# LoRa_1W_Breakout_433MHz.net
KiCad netlist of a schematic drawn in EAGLE
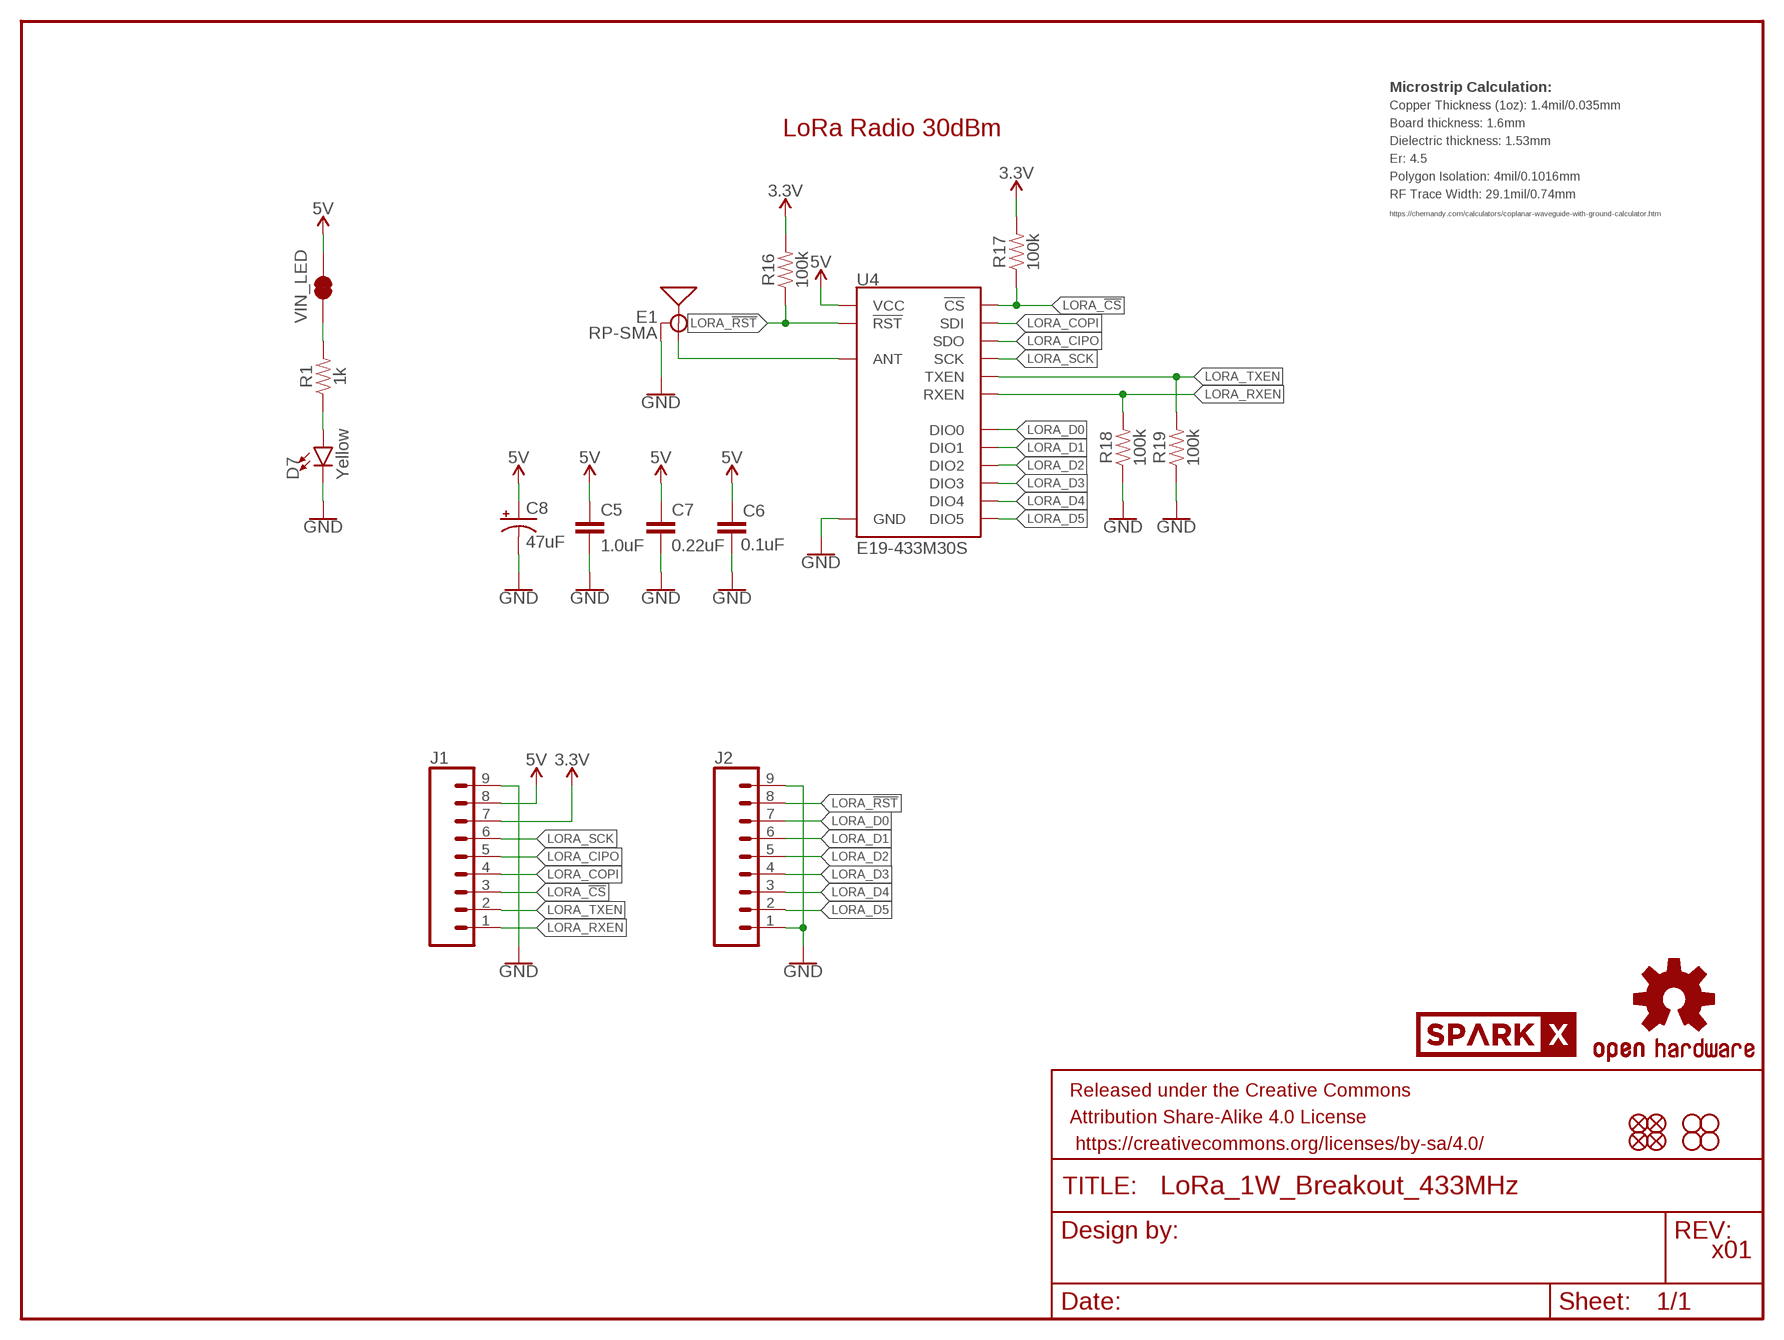
[diagram p0: schematic, sheet 1]

(export (version "E")
  (design (tool "Eeschema 10.0.6"))
  (components
    (comp (ref "C5")
      (value "1.0uF")
      (footprint "eagle-import:0603")
      (libsource (lib "eagle-import") (part "1.0UF-0603-16V-10%"))
    )
    (comp (ref "C6")
      (value "0.1uF")
      (footprint "eagle-import:0603")
      (libsource (lib "eagle-import") (part "0.1UF-0603-25V-(+80/-20%)"))
    )
    (comp (ref "C7")
      (value "0.22uF")
      (footprint "eagle-import:0603")
      (libsource (lib "eagle-import") (part "0.22UF-0603-25V-10%"))
    )
    (comp (ref "C8")
      (value "47uF")
      (footprint "eagle-import:EIA3528")
      (libsource (lib "eagle-import") (part "47UF-POLAR-EIA3528-10V-10%"))
    )
    (comp (ref "D7")
      (value "Yellow")
      (footprint "eagle-import:LED-0603")
      (libsource (lib "eagle-import") (part "LED-YELLOW0603"))
    )
    (comp (ref "E1")
      (value "RP-SMA")
      (footprint "eagle-import:SMA-EDGE")
      (libsource (lib "eagle-import") (part "ANTENNA-SMA-GROUNDEDEDGE_RPSMA"))
    )
    (comp (ref "FD1")
      (value "FIDUCIALUFIDUCIAL")
      (footprint "eagle-import:FIDUCIAL-MICRO")
      (libsource (lib "eagle-import") (part "FIDUCIALUFIDUCIAL"))
    )
    (comp (ref "FD2")
      (value "FIDUCIALUFIDUCIAL")
      (footprint "eagle-import:FIDUCIAL-MICRO")
      (libsource (lib "eagle-import") (part "FIDUCIALUFIDUCIAL"))
    )
    (comp (ref "FD3")
      (value "FIDUCIALUFIDUCIAL")
      (footprint "eagle-import:FIDUCIAL-MICRO")
      (libsource (lib "eagle-import") (part "FIDUCIALUFIDUCIAL"))
    )
    (comp (ref "FD4")
      (value "FIDUCIALUFIDUCIAL")
      (footprint "eagle-import:FIDUCIAL-MICRO")
      (libsource (lib "eagle-import") (part "FIDUCIALUFIDUCIAL"))
    )
    (comp (ref "FRAME2")
      (value "FRAME-LETTER")
      (footprint "eagle-import:CREATIVE_COMMONS")
      (libsource (lib "eagle-import") (part "FRAME-LETTER"))
    )
    (comp (ref "H1")
      (value "STAND-OFF")
      (footprint "eagle-import:STAND-OFF")
      (libsource (lib "eagle-import") (part "STAND-OFF"))
    )
    (comp (ref "H2")
      (value "STAND-OFF")
      (footprint "eagle-import:STAND-OFF")
      (libsource (lib "eagle-import") (part "STAND-OFF"))
    )
    (comp (ref "H3")
      (value "STAND-OFF")
      (footprint "eagle-import:STAND-OFF")
      (libsource (lib "eagle-import") (part "STAND-OFF"))
    )
    (comp (ref "H4")
      (value "STAND-OFF")
      (footprint "eagle-import:STAND-OFF")
      (libsource (lib "eagle-import") (part "STAND-OFF"))
    )
    (comp (ref "J1")
      (value "CONN_09NO_SILK")
      (footprint "eagle-import:1X09_NO_SILK")
      (libsource (lib "eagle-import") (part "CONN_09NO_SILK"))
    )
    (comp (ref "J2")
      (value "CONN_09NO_SILK")
      (footprint "eagle-import:1X09_NO_SILK")
      (libsource (lib "eagle-import") (part "CONN_09NO_SILK"))
    )
    (comp (ref "LOGO3")
      (value "OSHW-LOGOMINI")
      (footprint "eagle-import:OSHW-LOGO-MINI")
      (libsource (lib "eagle-import") (part "OSHW-LOGOMINI"))
    )
    (comp (ref "R1")
      (value "1k")
      (footprint "eagle-import:0603")
      (libsource (lib "eagle-import") (part "1KOHM-0603-1/10W-1%"))
    )
    (comp (ref "R16")
      (value "100k")
      (footprint "eagle-import:0603")
      (libsource (lib "eagle-import") (part "100KOHM-0603-1/10W-1%"))
    )
    (comp (ref "R17")
      (value "100k")
      (footprint "eagle-import:0603")
      (libsource (lib "eagle-import") (part "100KOHM-0603-1/10W-1%"))
    )
    (comp (ref "R18")
      (value "100k")
      (footprint "eagle-import:0603")
      (libsource (lib "eagle-import") (part "100KOHM-0603-1/10W-1%"))
    )
    (comp (ref "R19")
      (value "100k")
      (footprint "eagle-import:0603")
      (libsource (lib "eagle-import") (part "100KOHM-0603-1/10W-1%"))
    )
    (comp (ref "U$5")
      (value "SPARKX-LOGO5")
      (footprint "eagle-import:SPARKX-LARGE")
      (libsource (lib "eagle-import") (part "SPARKX-LOGO5"))
    )
    (comp (ref "U4")
      (value "E19-433M30S")
      (footprint "eagle-import:E19-433M30S")
      (libsource (lib "eagle-import") (part "LORA-E19433MHZ"))
    )
    (comp (ref "VIN_LED")
      (value "JUMPER-SMT_2_NC_TRACE_SILK")
      (footprint "eagle-import:SMT-JUMPER_2_NC_TRACE_SILK")
      (libsource (lib "eagle-import") (part "JUMPER-SMT_2_NC_TRACE_SILK"))
    )
  )
  (nets
    (net (code "1") (name "/LORA_~{CS}") (class "Default")
      (node (ref "J1") (pin "3") (pinfunction "3_3") (pintype "passive"))
      (node (ref "R17") (pin "1") (pinfunction "1_1") (pintype "passive"))
      (node (ref "U4") (pin "15") (pinfunction "~{CS}_15") (pintype "bidirectional"))
    )
    (net (code "2") (name "/LORA_~{RST}") (class "Default")
      (node (ref "J2") (pin "8") (pinfunction "8_8") (pintype "passive"))
      (node (ref "R16") (pin "1") (pinfunction "1_1") (pintype "passive"))
      (node (ref "U4") (pin "8") (pinfunction "~{RST}_8") (pintype "bidirectional"))
    )
    (net (code "3") (name "3.3V") (class "Default")
      (node (ref "J1") (pin "7") (pinfunction "7_7") (pintype "passive"))
      (node (ref "R16") (pin "2") (pinfunction "2_2") (pintype "passive"))
      (node (ref "R17") (pin "2") (pinfunction "2_2") (pintype "passive"))
    )
    (net (code "4") (name "5V") (class "Default")
      (node (ref "C5") (pin "1") (pinfunction "1_1") (pintype "passive"))
      (node (ref "C6") (pin "1") (pinfunction "1_1") (pintype "passive"))
      (node (ref "C7") (pin "1") (pinfunction "1_1") (pintype "passive"))
      (node (ref "C8") (pin "A") (pinfunction "+_A") (pintype "passive"))
      (node (ref "J1") (pin "8") (pinfunction "8_8") (pintype "passive"))
      (node (ref "U4") (pin "11") (pinfunction "VCC_11") (pintype "bidirectional"))
      (node (ref "VIN_LED") (pin "2") (pinfunction "2_2") (pintype "passive"))
    )
    (net (code "5") (name "GND") (class "Default")
      (node (ref "C5") (pin "2") (pinfunction "2_2") (pintype "passive"))
      (node (ref "C6") (pin "2") (pinfunction "2_2") (pintype "passive"))
      (node (ref "C7") (pin "2") (pinfunction "2_2") (pintype "passive"))
      (node (ref "C8") (pin "C") (pinfunction "-_C") (pintype "passive"))
      (node (ref "D7") (pin "C") (pinfunction "C_C") (pintype "passive"))
      (node (ref "E1") (pin "GND@0") (pinfunction "GND_GND@0") (pintype "bidirectional"))
      (node (ref "E1") (pin "GND@1") (pinfunction "GND_GND@1") (pintype "bidirectional"))
      (node (ref "E1") (pin "GND@2") (pinfunction "GND_GND@2") (pintype "bidirectional"))
      (node (ref "E1") (pin "GND@3") (pinfunction "GND_GND@3") (pintype "bidirectional"))
      (node (ref "J1") (pin "9") (pinfunction "9_9") (pintype "passive"))
      (node (ref "J2") (pin "1") (pinfunction "1_1") (pintype "passive"))
      (node (ref "J2") (pin "9") (pinfunction "9_9") (pintype "passive"))
      (node (ref "R18") (pin "1") (pinfunction "1_1") (pintype "passive"))
      (node (ref "R19") (pin "1") (pinfunction "1_1") (pintype "passive"))
      (node (ref "U4") (pin "1") (pinfunction "GND_1") (pintype "bidirectional"))
      (node (ref "U4") (pin "10") (pinfunction "GND_10") (pintype "bidirectional"))
      (node (ref "U4") (pin "18") (pinfunction "GND_18") (pintype "bidirectional"))
      (node (ref "U4") (pin "20") (pinfunction "GND_20") (pintype "bidirectional"))
      (node (ref "U4") (pin "21") (pinfunction "GND_21") (pintype "bidirectional"))
      (node (ref "U4") (pin "22") (pinfunction "GND_22") (pintype "bidirectional"))
      (node (ref "U4") (pin "9") (pinfunction "GND_9") (pintype "bidirectional"))
    )
    (net (code "6") (name "LORA_CIPO") (class "Default")
      (node (ref "J1") (pin "5") (pinfunction "5_5") (pintype "passive"))
      (node (ref "U4") (pin "13") (pinfunction "SDO_13") (pintype "bidirectional"))
    )
    (net (code "7") (name "LORA_COPI") (class "Default")
      (node (ref "J1") (pin "4") (pinfunction "4_4") (pintype "passive"))
      (node (ref "U4") (pin "14") (pinfunction "SDI_14") (pintype "bidirectional"))
    )
    (net (code "8") (name "LORA_D0") (class "Default")
      (node (ref "J2") (pin "7") (pinfunction "7_7") (pintype "passive"))
      (node (ref "U4") (pin "7") (pinfunction "DIO0_7") (pintype "bidirectional"))
    )
    (net (code "9") (name "LORA_D1") (class "Default")
      (node (ref "J2") (pin "6") (pinfunction "6_6") (pintype "passive"))
      (node (ref "U4") (pin "6") (pinfunction "DIO1_6") (pintype "bidirectional"))
    )
    (net (code "10") (name "LORA_D2") (class "Default")
      (node (ref "J2") (pin "5") (pinfunction "5_5") (pintype "passive"))
      (node (ref "U4") (pin "5") (pinfunction "DIO2_5") (pintype "bidirectional"))
    )
    (net (code "11") (name "LORA_D3") (class "Default")
      (node (ref "J2") (pin "4") (pinfunction "4_4") (pintype "passive"))
      (node (ref "U4") (pin "4") (pinfunction "DIO3_4") (pintype "bidirectional"))
    )
    (net (code "12") (name "LORA_D4") (class "Default")
      (node (ref "J2") (pin "3") (pinfunction "3_3") (pintype "passive"))
      (node (ref "U4") (pin "3") (pinfunction "DIO4_3") (pintype "bidirectional"))
    )
    (net (code "13") (name "LORA_D5") (class "Default")
      (node (ref "J2") (pin "2") (pinfunction "2_2") (pintype "passive"))
      (node (ref "U4") (pin "2") (pinfunction "DIO5_2") (pintype "bidirectional"))
    )
    (net (code "14") (name "LORA_RXEN") (class "Default")
      (node (ref "J1") (pin "1") (pinfunction "1_1") (pintype "passive"))
      (node (ref "R18") (pin "2") (pinfunction "2_2") (pintype "passive"))
      (node (ref "U4") (pin "17") (pinfunction "RXEN_17") (pintype "bidirectional"))
    )
    (net (code "15") (name "LORA_SCK") (class "Default")
      (node (ref "J1") (pin "6") (pinfunction "6_6") (pintype "passive"))
      (node (ref "U4") (pin "12") (pinfunction "SCK_12") (pintype "bidirectional"))
    )
    (net (code "16") (name "LORA_TXEN") (class "Default")
      (node (ref "J1") (pin "2") (pinfunction "2_2") (pintype "passive"))
      (node (ref "R19") (pin "2") (pinfunction "2_2") (pintype "passive"))
      (node (ref "U4") (pin "16") (pinfunction "TXEN_16") (pintype "bidirectional"))
    )
    (net (code "17") (name "Net-(D7-PadA)") (class "Default")
      (node (ref "D7") (pin "A") (pinfunction "A_A") (pintype "passive"))
      (node (ref "R1") (pin "1") (pinfunction "1_1") (pintype "passive"))
    )
    (net (code "18") (name "Net-(E1-SIGNAL)") (class "Default")
      (node (ref "E1") (pin "SIG") (pinfunction "SIGNAL_SIG") (pintype "bidirectional"))
      (node (ref "U4") (pin "19") (pinfunction "ANT_19") (pintype "bidirectional"))
    )
    (net (code "19") (name "Net-(R1-Pad2)") (class "Default")
      (node (ref "R1") (pin "2") (pinfunction "2_2") (pintype "passive"))
      (node (ref "VIN_LED") (pin "1") (pinfunction "1_1") (pintype "passive"))
    )
  )
)
